# sh.net
KiCad netlist of a schematic drawn in EAGLE
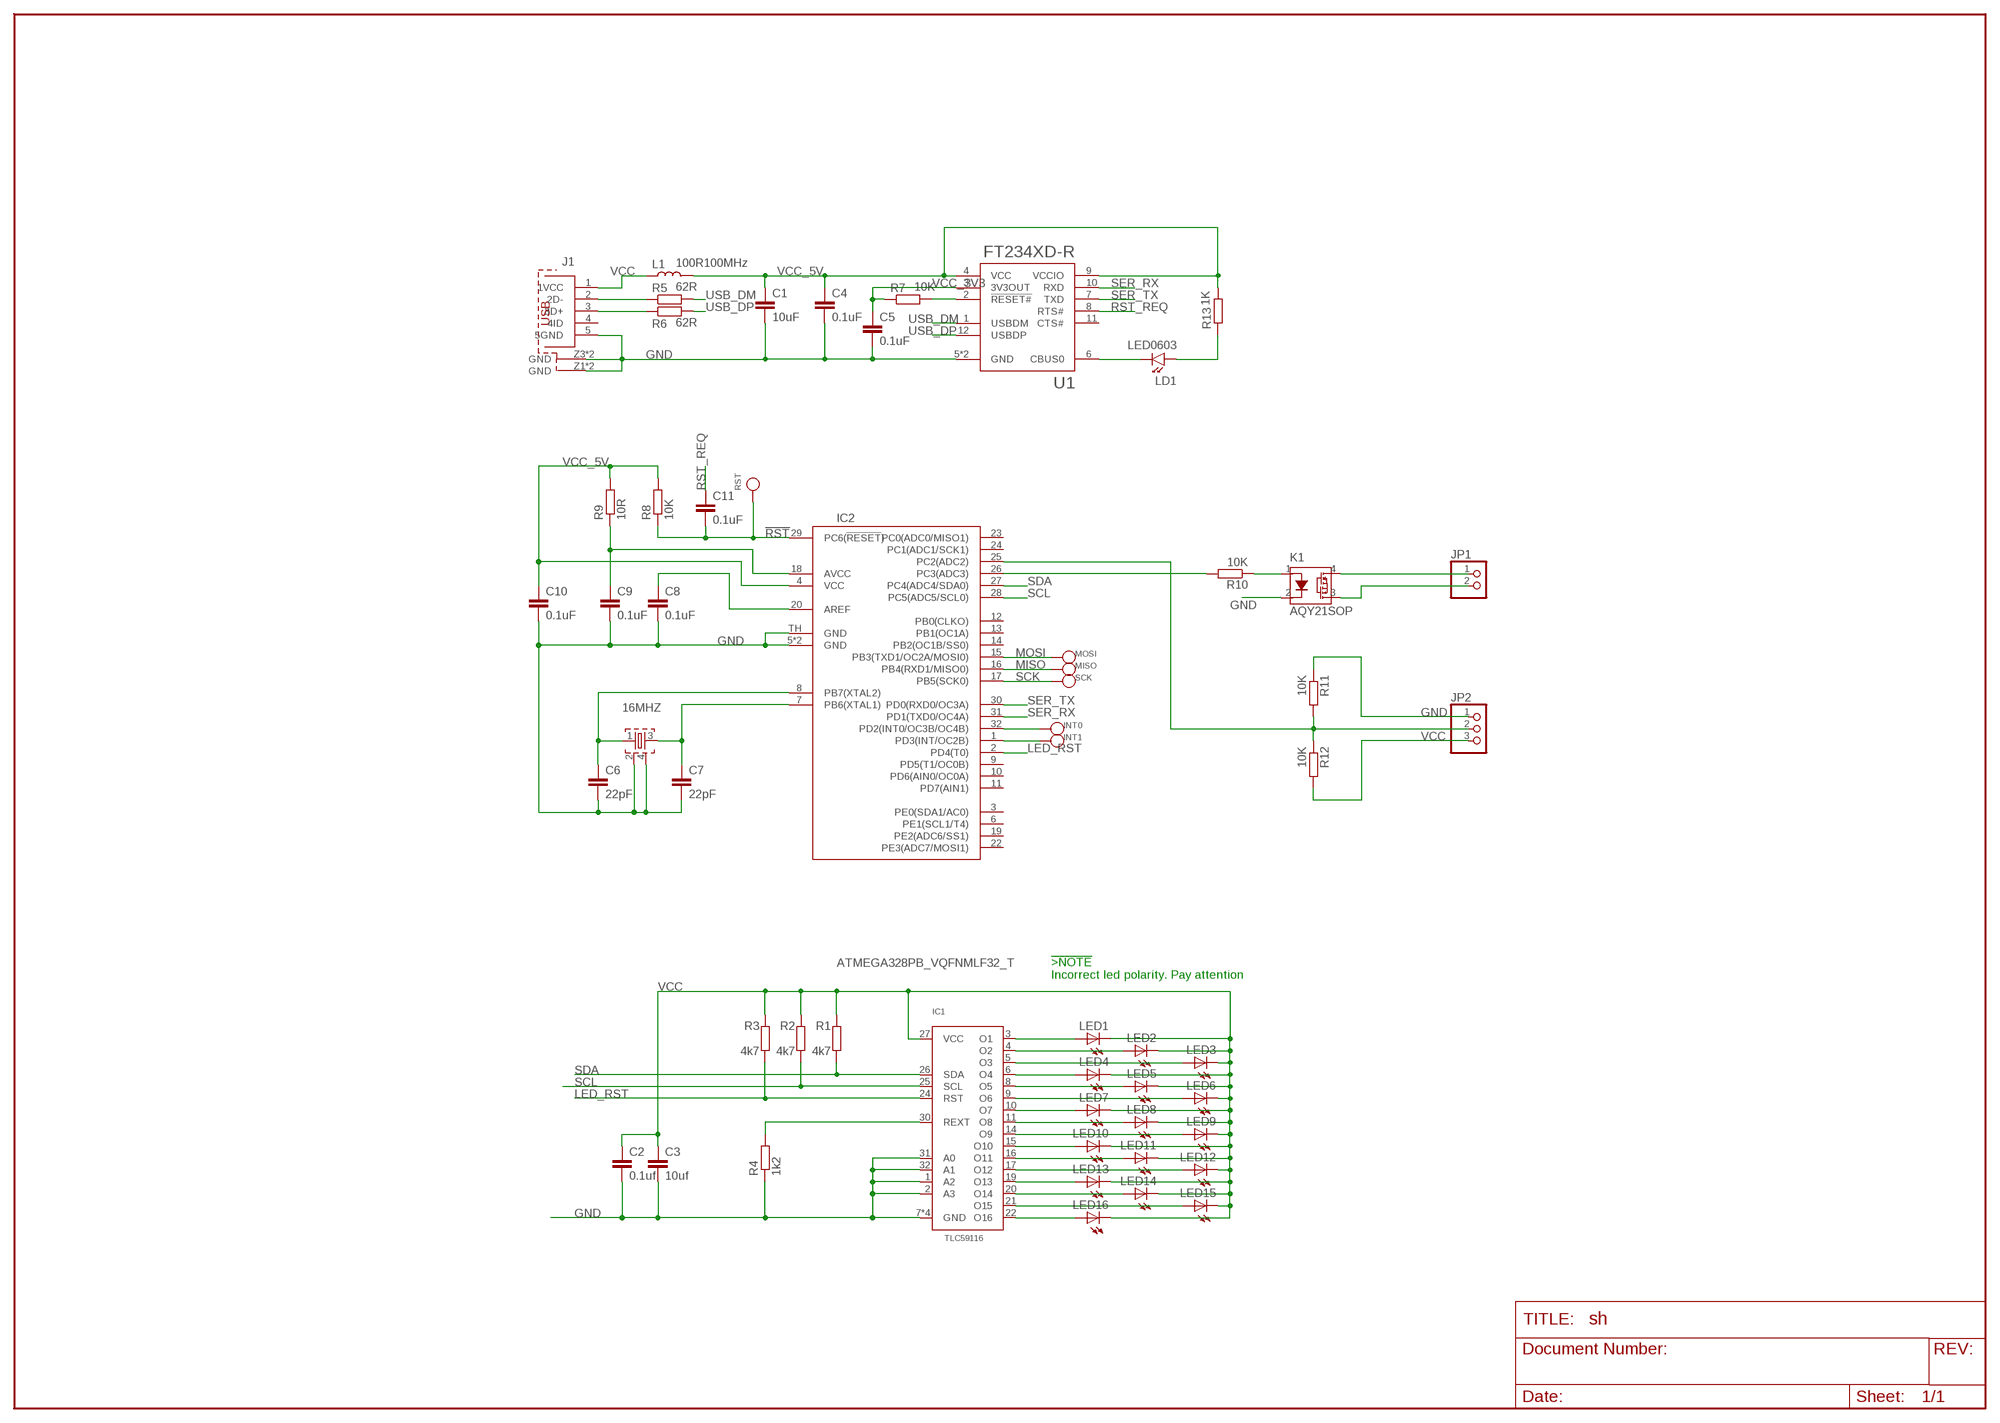
[diagram p0: schematic, sheet 1]

(export (version "E")
  (design (tool "Eeschema 10.0.6"))
  (components
    (comp (ref "16MHZ")
      (value "QUARTZ_ZQ")
      (footprint "eagle-import:QUARTZ_3X3MM")
      (libsource (lib "eagle-import") (part "QUARTZ_ZQ"))
    )
    (comp (ref "C1")
      (value "10uF")
      (footprint "eagle-import:1206")
      (libsource (lib "eagle-import") (part "SMD_C1206"))
    )
    (comp (ref "C2")
      (value "0.1uf")
      (footprint "eagle-import:0603")
      (libsource (lib "eagle-import") (part "SMD_C0603"))
    )
    (comp (ref "C3")
      (value "10uf")
      (footprint "eagle-import:1206")
      (libsource (lib "eagle-import") (part "SMD_C1206"))
    )
    (comp (ref "C4")
      (value "0.1uF")
      (footprint "eagle-import:0603")
      (libsource (lib "eagle-import") (part "SMD_C0603"))
    )
    (comp (ref "C5")
      (value "0.1uF")
      (footprint "eagle-import:0603")
      (libsource (lib "eagle-import") (part "SMD_C0603"))
    )
    (comp (ref "C6")
      (value "22pF")
      (footprint "eagle-import:0603")
      (libsource (lib "eagle-import") (part "SMD_C0603"))
    )
    (comp (ref "C7")
      (value "22pF")
      (footprint "eagle-import:0603")
      (libsource (lib "eagle-import") (part "SMD_C0603"))
    )
    (comp (ref "C8")
      (value "0.1uF")
      (footprint "eagle-import:0603")
      (libsource (lib "eagle-import") (part "SMD_C0603"))
    )
    (comp (ref "C9")
      (value "0.1uF")
      (footprint "eagle-import:0603")
      (libsource (lib "eagle-import") (part "SMD_C0603"))
    )
    (comp (ref "C10")
      (value "0.1uF")
      (footprint "eagle-import:0603")
      (libsource (lib "eagle-import") (part "SMD_C0603"))
    )
    (comp (ref "C11")
      (value "0.1uF")
      (footprint "eagle-import:0603")
      (libsource (lib "eagle-import") (part "SMD_C0603"))
    )
    (comp (ref "IC1")
      (value "TLC59116")
      (footprint "eagle-import:MLF32-TH")
      (libsource (lib "eagle-import") (part "TLC59116"))
    )
    (comp (ref "IC2")
      (value "ATMEGA328PB_VQFNMLF32_T")
      (footprint "eagle-import:MLF32-TH")
      (libsource (lib "eagle-import") (part "ATMEGA328PB_VQFNMLF32_T"))
    )
    (comp (ref "INT0")
      (value "TEST_POINT_D2MM")
      (footprint "eagle-import:TP")
      (libsource (lib "eagle-import") (part "TEST_POINT_D2MM"))
    )
    (comp (ref "INT1")
      (value "TEST_POINT_D2MM")
      (footprint "eagle-import:TP")
      (libsource (lib "eagle-import") (part "TEST_POINT_D2MM"))
    )
    (comp (ref "J1")
      (value "MINI_USB_TYP_B_@")
      (footprint "eagle-import:65100516121")
      (libsource (lib "eagle-import") (part "MINI_USB_TYP_B_@"))
    )
    (comp (ref "JP1")
      (value "PINHD-1X2LIGHT")
      (footprint "eagle-import:2X01")
      (libsource (lib "eagle-import") (part "PINHD-1X2LIGHT"))
    )
    (comp (ref "JP2")
      (value "PINHD-1X3_LIGHT")
      (footprint "eagle-import:3X01")
      (libsource (lib "eagle-import") (part "PINHD-1X3_LIGHT"))
    )
    (comp (ref "K1")
      (value "AQY21SOP")
      (footprint "eagle-import:SOP04")
      (libsource (lib "eagle-import") (part "AQYSOP21"))
    )
    (comp (ref "L1")
      (value "100R100MHz")
      (footprint "eagle-import:0805")
      (libsource (lib "eagle-import") (part "SMD_L"))
    )
    (comp (ref "LD1")
      (value "LED0603")
      (footprint "eagle-import:0603_P")
      (libsource (lib "eagle-import") (part "LED0603"))
    )
    (comp (ref "LED1")
      (value "LED2KA-3528ASYC")
      (footprint "eagle-import:KA-3528ASYC")
      (libsource (lib "eagle-import") (part "LED2KA-3528ASYC"))
    )
    (comp (ref "LED2")
      (value "LED2KA-3528ASYC")
      (footprint "eagle-import:KA-3528ASYC")
      (libsource (lib "eagle-import") (part "LED2KA-3528ASYC"))
    )
    (comp (ref "LED3")
      (value "LED2KA-3528ASYC")
      (footprint "eagle-import:KA-3528ASYC")
      (libsource (lib "eagle-import") (part "LED2KA-3528ASYC"))
    )
    (comp (ref "LED4")
      (value "LED2KA-3528ASYC")
      (footprint "eagle-import:KA-3528ASYC")
      (libsource (lib "eagle-import") (part "LED2KA-3528ASYC"))
    )
    (comp (ref "LED5")
      (value "LED2KA-3528ASYC")
      (footprint "eagle-import:KA-3528ASYC")
      (libsource (lib "eagle-import") (part "LED2KA-3528ASYC"))
    )
    (comp (ref "LED6")
      (value "LED2KA-3528ASYC")
      (footprint "eagle-import:KA-3528ASYC")
      (libsource (lib "eagle-import") (part "LED2KA-3528ASYC"))
    )
    (comp (ref "LED7")
      (value "LED2KA-3528ASYC")
      (footprint "eagle-import:KA-3528ASYC")
      (libsource (lib "eagle-import") (part "LED2KA-3528ASYC"))
    )
    (comp (ref "LED8")
      (value "LED2KA-3528ASYC")
      (footprint "eagle-import:KA-3528ASYC")
      (libsource (lib "eagle-import") (part "LED2KA-3528ASYC"))
    )
    (comp (ref "LED9")
      (value "LED2KA-3528ASYC")
      (footprint "eagle-import:KA-3528ASYC")
      (libsource (lib "eagle-import") (part "LED2KA-3528ASYC"))
    )
    (comp (ref "LED10")
      (value "LED2KA-3528ASYC")
      (footprint "eagle-import:KA-3528ASYC")
      (libsource (lib "eagle-import") (part "LED2KA-3528ASYC"))
    )
    (comp (ref "LED11")
      (value "LED2KA-3528ASYC")
      (footprint "eagle-import:KA-3528ASYC")
      (libsource (lib "eagle-import") (part "LED2KA-3528ASYC"))
    )
    (comp (ref "LED12")
      (value "LED2KA-3528ASYC")
      (footprint "eagle-import:KA-3528ASYC")
      (libsource (lib "eagle-import") (part "LED2KA-3528ASYC"))
    )
    (comp (ref "LED13")
      (value "LED2KA-3528ASYC")
      (footprint "eagle-import:KA-3528ASYC")
      (libsource (lib "eagle-import") (part "LED2KA-3528ASYC"))
    )
    (comp (ref "LED14")
      (value "LED2KA-3528ASYC")
      (footprint "eagle-import:KA-3528ASYC")
      (libsource (lib "eagle-import") (part "LED2KA-3528ASYC"))
    )
    (comp (ref "LED15")
      (value "LED2KA-3528ASYC")
      (footprint "eagle-import:KA-3528ASYC")
      (libsource (lib "eagle-import") (part "LED2KA-3528ASYC"))
    )
    (comp (ref "LED16")
      (value "LED2KA-3528ASYC")
      (footprint "eagle-import:KA-3528ASYC")
      (libsource (lib "eagle-import") (part "LED2KA-3528ASYC"))
    )
    (comp (ref "MISO")
      (value "TEST_POINT_D2MM")
      (footprint "eagle-import:TP")
      (libsource (lib "eagle-import") (part "TEST_POINT_D2MM"))
    )
    (comp (ref "MOSI")
      (value "TEST_POINT_D2MM")
      (footprint "eagle-import:TP")
      (libsource (lib "eagle-import") (part "TEST_POINT_D2MM"))
    )
    (comp (ref "R1")
      (value "4k7")
      (footprint "eagle-import:0603")
      (libsource (lib "eagle-import") (part "SMD_R0603"))
    )
    (comp (ref "R2")
      (value "4k7")
      (footprint "eagle-import:0603")
      (libsource (lib "eagle-import") (part "SMD_R0603"))
    )
    (comp (ref "R3")
      (value "4k7")
      (footprint "eagle-import:0603")
      (libsource (lib "eagle-import") (part "SMD_R0603"))
    )
    (comp (ref "R4")
      (value "1k2")
      (footprint "eagle-import:0603")
      (libsource (lib "eagle-import") (part "SMD_R0603"))
    )
    (comp (ref "R5")
      (value "62R")
      (footprint "eagle-import:0603")
      (libsource (lib "eagle-import") (part "SMD_R0603"))
    )
    (comp (ref "R6")
      (value "62R")
      (footprint "eagle-import:0603")
      (libsource (lib "eagle-import") (part "SMD_R0603"))
    )
    (comp (ref "R7")
      (value "10K")
      (footprint "eagle-import:0603")
      (libsource (lib "eagle-import") (part "SMD_R0603"))
    )
    (comp (ref "R8")
      (value "10K")
      (footprint "eagle-import:0603")
      (libsource (lib "eagle-import") (part "SMD_R0603"))
    )
    (comp (ref "R9")
      (value "10R")
      (footprint "eagle-import:0603")
      (libsource (lib "eagle-import") (part "SMD_R0603"))
    )
    (comp (ref "R10")
      (value "10K")
      (footprint "eagle-import:0603")
      (libsource (lib "eagle-import") (part "SMD_R0603"))
    )
    (comp (ref "R11")
      (value "10K")
      (footprint "eagle-import:0603")
      (libsource (lib "eagle-import") (part "SMD_R0603"))
    )
    (comp (ref "R12")
      (value "10K")
      (footprint "eagle-import:0603")
      (libsource (lib "eagle-import") (part "SMD_R0603"))
    )
    (comp (ref "R13")
      (value "1K")
      (footprint "eagle-import:0603")
      (libsource (lib "eagle-import") (part "SMD_R0603"))
    )
    (comp (ref "RST")
      (value "TEST_POINT_D2MM")
      (footprint "eagle-import:TP")
      (libsource (lib "eagle-import") (part "TEST_POINT_D2MM"))
    )
    (comp (ref "SCK")
      (value "TEST_POINT_D2MM")
      (footprint "eagle-import:TP")
      (libsource (lib "eagle-import") (part "TEST_POINT_D2MM"))
    )
    (comp (ref "U1")
      (value "FT234XD-R")
      (footprint "eagle-import:IC_FT234XD-R")
      (fields (field (name "MF") "FTDI,"))
      (libsource (lib "eagle-import") (part "FT234XD-R"))
    )
  )
  (nets
    (net (code "1") (name "/GND") (class "Default")
      (node (ref "16MHZ") (pin "2") (pinfunction "2_2") (pintype "passive"))
      (node (ref "16MHZ") (pin "4") (pinfunction "4_4") (pintype "passive"))
      (node (ref "C1") (pin "2") (pinfunction "2_2") (pintype "passive"))
      (node (ref "C10") (pin "2") (pinfunction "2_2") (pintype "passive"))
      (node (ref "C2") (pin "2") (pinfunction "2_2") (pintype "passive"))
      (node (ref "C3") (pin "2") (pinfunction "2_2") (pintype "passive"))
      (node (ref "C4") (pin "2") (pinfunction "2_2") (pintype "passive"))
      (node (ref "C5") (pin "2") (pinfunction "2_2") (pintype "passive"))
      (node (ref "C6") (pin "2") (pinfunction "2_2") (pintype "passive"))
      (node (ref "C7") (pin "2") (pinfunction "2_2") (pintype "passive"))
      (node (ref "C8") (pin "2") (pinfunction "2_2") (pintype "passive"))
      (node (ref "C9") (pin "2") (pinfunction "2_2") (pintype "passive"))
      (node (ref "IC1") (pin "1") (pinfunction "A2_1") (pintype "bidirectional"))
      (node (ref "IC1") (pin "18") (pinfunction "GND_18") (pintype "bidirectional"))
      (node (ref "IC1") (pin "2") (pinfunction "A3_2") (pintype "bidirectional"))
      (node (ref "IC1") (pin "23") (pinfunction "GND_23") (pintype "bidirectional"))
      (node (ref "IC1") (pin "31") (pinfunction "A0_31") (pintype "bidirectional"))
      (node (ref "IC1") (pin "32") (pinfunction "A1_32") (pintype "bidirectional"))
      (node (ref "IC1") (pin "7") (pinfunction "GND_7") (pintype "bidirectional"))
      (node (ref "IC1") (pin "TH") (pinfunction "GND_TH") (pintype "bidirectional"))
      (node (ref "IC2") (pin "21") (pinfunction "GND_21") (pintype "power_in"))
      (node (ref "IC2") (pin "5") (pinfunction "GND_5") (pintype "power_in"))
      (node (ref "IC2") (pin "TH") (pinfunction "GND_TH") (pintype "power_in"))
      (node (ref "J1") (pin "5") (pinfunction "5GND_5") (pintype "passive"))
      (node (ref "J1") (pin "Z1") (pinfunction "GND_Z1") (pintype "bidirectional"))
      (node (ref "J1") (pin "Z2") (pinfunction "GND_Z2") (pintype "bidirectional"))
      (node (ref "J1") (pin "Z3") (pinfunction "GND_Z3") (pintype "bidirectional"))
      (node (ref "J1") (pin "Z4") (pinfunction "GND_Z4") (pintype "bidirectional"))
      (node (ref "JP2") (pin "1") (pinfunction "1_1") (pintype "passive"))
      (node (ref "K1") (pin "2") (pinfunction "K_2") (pintype "passive"))
      (node (ref "R11") (pin "1") (pinfunction "1_1") (pintype "passive"))
      (node (ref "R4") (pin "1") (pinfunction "1_1") (pintype "passive"))
      (node (ref "U1") (pin "13") (pinfunction "GND_13") (pintype "power_in"))
      (node (ref "U1") (pin "5") (pinfunction "GND_5") (pintype "power_in"))
    )
    (net (code "2") (name "/LED_RST") (class "Default")
      (node (ref "IC1") (pin "24") (pinfunction "RST_24") (pintype "bidirectional"))
      (node (ref "IC2") (pin "2") (pinfunction "PD4(T0)_2") (pintype "bidirectional"))
      (node (ref "R3") (pin "1") (pinfunction "1_1") (pintype "passive"))
    )
    (net (code "3") (name "/MISO") (class "Default")
      (node (ref "IC2") (pin "16") (pinfunction "PB4(RXD1/MISO0)_16") (pintype "bidirectional"))
      (node (ref "MISO") (pin "P$1") (pinfunction "1_P$1") (pintype "bidirectional"))
    )
    (net (code "4") (name "/MOSI") (class "Default")
      (node (ref "IC2") (pin "15") (pinfunction "PB3(TXD1/OC2A/MOSI0)_15") (pintype "bidirectional"))
      (node (ref "MOSI") (pin "P$1") (pinfunction "1_P$1") (pintype "bidirectional"))
    )
    (net (code "5") (name "/RST_REQ") (class "Default")
      (node (ref "C11") (pin "1") (pinfunction "1_1") (pintype "passive"))
      (node (ref "U1") (pin "8") (pinfunction "RTS#_8") (pintype "output"))
    )
    (net (code "6") (name "/SCK") (class "Default")
      (node (ref "IC2") (pin "17") (pinfunction "PB5(SCK0)_17") (pintype "bidirectional"))
      (node (ref "SCK") (pin "P$1") (pinfunction "1_P$1") (pintype "bidirectional"))
    )
    (net (code "7") (name "/SCL") (class "Default")
      (node (ref "IC1") (pin "25") (pinfunction "SCL_25") (pintype "bidirectional"))
      (node (ref "IC2") (pin "28") (pinfunction "PC5(ADC5/SCL0)_28") (pintype "bidirectional"))
      (node (ref "R2") (pin "1") (pinfunction "1_1") (pintype "passive"))
    )
    (net (code "8") (name "/SDA") (class "Default")
      (node (ref "IC1") (pin "26") (pinfunction "SDA_26") (pintype "bidirectional"))
      (node (ref "IC2") (pin "27") (pinfunction "PC4(ADC4/SDA0)_27") (pintype "bidirectional"))
      (node (ref "R1") (pin "1") (pinfunction "1_1") (pintype "passive"))
    )
    (net (code "9") (name "/SER_RX") (class "Default")
      (node (ref "IC2") (pin "31") (pinfunction "PD1(TXD0/OC4A)_31") (pintype "bidirectional"))
      (node (ref "U1") (pin "10") (pinfunction "RXD_10") (pintype "input"))
    )
    (net (code "10") (name "/SER_TX") (class "Default")
      (node (ref "IC2") (pin "30") (pinfunction "PD0(RXD0/OC3A)_30") (pintype "bidirectional"))
      (node (ref "U1") (pin "7") (pinfunction "TXD_7") (pintype "output"))
    )
    (net (code "11") (name "/USB_DM") (class "Default")
      (node (ref "R5") (pin "2") (pinfunction "2_2") (pintype "passive"))
      (node (ref "U1") (pin "1") (pinfunction "USBDM_1") (pintype "bidirectional"))
    )
    (net (code "12") (name "/USB_DP") (class "Default")
      (node (ref "R6") (pin "2") (pinfunction "2_2") (pintype "passive"))
      (node (ref "U1") (pin "12") (pinfunction "USBDP_12") (pintype "bidirectional"))
    )
    (net (code "13") (name "/VCC") (class "Default")
      (node (ref "C2") (pin "1") (pinfunction "1_1") (pintype "passive"))
      (node (ref "C3") (pin "1") (pinfunction "1_1") (pintype "passive"))
      (node (ref "IC1") (pin "27") (pinfunction "VCC_27") (pintype "bidirectional"))
      (node (ref "J1") (pin "1") (pinfunction "1VCC_1") (pintype "passive"))
      (node (ref "JP2") (pin "3") (pinfunction "3_3") (pintype "passive"))
      (node (ref "L1") (pin "1") (pinfunction "1_1") (pintype "passive"))
      (node (ref "LED1") (pin "C") (pinfunction "C_C") (pintype "passive"))
      (node (ref "LED10") (pin "C") (pinfunction "C_C") (pintype "passive"))
      (node (ref "LED11") (pin "C") (pinfunction "C_C") (pintype "passive"))
      (node (ref "LED12") (pin "C") (pinfunction "C_C") (pintype "passive"))
      (node (ref "LED13") (pin "C") (pinfunction "C_C") (pintype "passive"))
      (node (ref "LED14") (pin "C") (pinfunction "C_C") (pintype "passive"))
      (node (ref "LED15") (pin "C") (pinfunction "C_C") (pintype "passive"))
      (node (ref "LED16") (pin "C") (pinfunction "C_C") (pintype "passive"))
      (node (ref "LED2") (pin "C") (pinfunction "C_C") (pintype "passive"))
      (node (ref "LED3") (pin "C") (pinfunction "C_C") (pintype "passive"))
      (node (ref "LED4") (pin "C") (pinfunction "C_C") (pintype "passive"))
      (node (ref "LED5") (pin "C") (pinfunction "C_C") (pintype "passive"))
      (node (ref "LED6") (pin "C") (pinfunction "C_C") (pintype "passive"))
      (node (ref "LED7") (pin "C") (pinfunction "C_C") (pintype "passive"))
      (node (ref "LED8") (pin "C") (pinfunction "C_C") (pintype "passive"))
      (node (ref "LED9") (pin "C") (pinfunction "C_C") (pintype "passive"))
      (node (ref "R1") (pin "2") (pinfunction "2_2") (pintype "passive"))
      (node (ref "R12") (pin "2") (pinfunction "2_2") (pintype "passive"))
      (node (ref "R2") (pin "2") (pinfunction "2_2") (pintype "passive"))
      (node (ref "R3") (pin "2") (pinfunction "2_2") (pintype "passive"))
    )
    (net (code "14") (name "/VCC_3V3") (class "Default")
      (node (ref "C5") (pin "1") (pinfunction "1_1") (pintype "passive"))
      (node (ref "R7") (pin "1") (pinfunction "1_1") (pintype "passive"))
      (node (ref "U1") (pin "3") (pinfunction "3V3OUT_3") (pintype "output"))
    )
    (net (code "15") (name "/VCC_5V") (class "Default")
      (node (ref "C1") (pin "1") (pinfunction "1_1") (pintype "passive"))
      (node (ref "C10") (pin "1") (pinfunction "1_1") (pintype "passive"))
      (node (ref "C4") (pin "1") (pinfunction "1_1") (pintype "passive"))
      (node (ref "IC2") (pin "4") (pinfunction "VCC_4") (pintype "power_in"))
      (node (ref "L1") (pin "2") (pinfunction "2_2") (pintype "passive"))
      (node (ref "R13") (pin "2") (pinfunction "2_2") (pintype "passive"))
      (node (ref "R8") (pin "2") (pinfunction "2_2") (pintype "passive"))
      (node (ref "R9") (pin "2") (pinfunction "2_2") (pintype "passive"))
      (node (ref "U1") (pin "4") (pinfunction "VCC_4") (pintype "power_in"))
      (node (ref "U1") (pin "9") (pinfunction "VCCIO_9") (pintype "power_in"))
    )
    (net (code "16") (name "/~{RST}") (class "Default")
      (node (ref "C11") (pin "2") (pinfunction "2_2") (pintype "passive"))
      (node (ref "IC2") (pin "29") (pinfunction "PC6(~{RESET})_29") (pintype "bidirectional"))
      (node (ref "R8") (pin "1") (pinfunction "1_1") (pintype "passive"))
      (node (ref "RST") (pin "P$1") (pinfunction "1_P$1") (pintype "bidirectional"))
    )
    (net (code "17") (name "Net-(IC1-O1)") (class "Default")
      (node (ref "IC1") (pin "3") (pinfunction "O1_3") (pintype "bidirectional"))
      (node (ref "LED1") (pin "A") (pinfunction "A_A") (pintype "passive"))
    )
    (net (code "18") (name "Net-(IC1-O2)") (class "Default")
      (node (ref "IC1") (pin "4") (pinfunction "O2_4") (pintype "bidirectional"))
      (node (ref "LED2") (pin "A") (pinfunction "A_A") (pintype "passive"))
    )
    (net (code "19") (name "Net-(IC1-O3)") (class "Default")
      (node (ref "IC1") (pin "5") (pinfunction "O3_5") (pintype "bidirectional"))
      (node (ref "LED3") (pin "A") (pinfunction "A_A") (pintype "passive"))
    )
    (net (code "20") (name "Net-(IC1-O4)") (class "Default")
      (node (ref "IC1") (pin "6") (pinfunction "O4_6") (pintype "bidirectional"))
      (node (ref "LED4") (pin "A") (pinfunction "A_A") (pintype "passive"))
    )
    (net (code "21") (name "Net-(IC1-O5)") (class "Default")
      (node (ref "IC1") (pin "8") (pinfunction "O5_8") (pintype "bidirectional"))
      (node (ref "LED5") (pin "A") (pinfunction "A_A") (pintype "passive"))
    )
    (net (code "22") (name "Net-(IC1-O6)") (class "Default")
      (node (ref "IC1") (pin "9") (pinfunction "O6_9") (pintype "bidirectional"))
      (node (ref "LED6") (pin "A") (pinfunction "A_A") (pintype "passive"))
    )
    (net (code "23") (name "Net-(IC1-O7)") (class "Default")
      (node (ref "IC1") (pin "10") (pinfunction "O7_10") (pintype "bidirectional"))
      (node (ref "LED7") (pin "A") (pinfunction "A_A") (pintype "passive"))
    )
    (net (code "24") (name "Net-(IC1-O8)") (class "Default")
      (node (ref "IC1") (pin "11") (pinfunction "O8_11") (pintype "bidirectional"))
      (node (ref "LED8") (pin "A") (pinfunction "A_A") (pintype "passive"))
    )
    (net (code "25") (name "Net-(IC1-O9)") (class "Default")
      (node (ref "IC1") (pin "14") (pinfunction "O9_14") (pintype "bidirectional"))
      (node (ref "LED9") (pin "A") (pinfunction "A_A") (pintype "passive"))
    )
    (net (code "26") (name "Net-(IC1-O10)") (class "Default")
      (node (ref "IC1") (pin "15") (pinfunction "O10_15") (pintype "bidirectional"))
      (node (ref "LED10") (pin "A") (pinfunction "A_A") (pintype "passive"))
    )
    (net (code "27") (name "Net-(IC1-O11)") (class "Default")
      (node (ref "IC1") (pin "16") (pinfunction "O11_16") (pintype "bidirectional"))
      (node (ref "LED11") (pin "A") (pinfunction "A_A") (pintype "passive"))
    )
    (net (code "28") (name "Net-(IC1-O12)") (class "Default")
      (node (ref "IC1") (pin "17") (pinfunction "O12_17") (pintype "bidirectional"))
      (node (ref "LED12") (pin "A") (pinfunction "A_A") (pintype "passive"))
    )
    (net (code "29") (name "Net-(IC1-O13)") (class "Default")
      (node (ref "IC1") (pin "19") (pinfunction "O13_19") (pintype "bidirectional"))
      (node (ref "LED13") (pin "A") (pinfunction "A_A") (pintype "passive"))
    )
    (net (code "30") (name "Net-(IC1-O14)") (class "Default")
      (node (ref "IC1") (pin "20") (pinfunction "O14_20") (pintype "bidirectional"))
      (node (ref "LED14") (pin "A") (pinfunction "A_A") (pintype "passive"))
    )
    (net (code "31") (name "Net-(IC1-O15)") (class "Default")
      (node (ref "IC1") (pin "21") (pinfunction "O15_21") (pintype "bidirectional"))
      (node (ref "LED15") (pin "A") (pinfunction "A_A") (pintype "passive"))
    )
    (net (code "32") (name "Net-(IC1-O16)") (class "Default")
      (node (ref "IC1") (pin "22") (pinfunction "O16_22") (pintype "bidirectional"))
      (node (ref "LED16") (pin "A") (pinfunction "A_A") (pintype "passive"))
    )
    (net (code "33") (name "Net-(IC1-REXT)") (class "Default")
      (node (ref "IC1") (pin "30") (pinfunction "REXT_30") (pintype "bidirectional"))
      (node (ref "R4") (pin "2") (pinfunction "2_2") (pintype "passive"))
    )
    (net (code "34") (name "Net-(IC2-AREF)") (class "Default")
      (node (ref "C8") (pin "1") (pinfunction "1_1") (pintype "passive"))
      (node (ref "IC2") (pin "20") (pinfunction "AREF_20") (pintype "passive"))
    )
    (net (code "35") (name "Net-(IC2-AVCC)") (class "Default")
      (node (ref "C9") (pin "1") (pinfunction "1_1") (pintype "passive"))
      (node (ref "IC2") (pin "18") (pinfunction "AVCC_18") (pintype "power_in"))
      (node (ref "R9") (pin "1") (pinfunction "1_1") (pintype "passive"))
    )
    (net (code "36") (name "Net-(IC2-PB6(XTAL1))") (class "Default")
      (node (ref "16MHZ") (pin "3") (pinfunction "3_3") (pintype "passive"))
      (node (ref "C7") (pin "1") (pinfunction "1_1") (pintype "passive"))
      (node (ref "IC2") (pin "7") (pinfunction "PB6(XTAL1)_7") (pintype "bidirectional"))
    )
    (net (code "37") (name "Net-(IC2-PB7(XTAL2))") (class "Default")
      (node (ref "16MHZ") (pin "1") (pinfunction "1_1") (pintype "passive"))
      (node (ref "C6") (pin "1") (pinfunction "1_1") (pintype "passive"))
      (node (ref "IC2") (pin "8") (pinfunction "PB7(XTAL2)_8") (pintype "bidirectional"))
    )
    (net (code "38") (name "Net-(IC2-PC2(ADC2))") (class "Default")
      (node (ref "IC2") (pin "25") (pinfunction "PC2(ADC2)_25") (pintype "bidirectional"))
      (node (ref "JP2") (pin "2") (pinfunction "2_2") (pintype "passive"))
      (node (ref "R11") (pin "2") (pinfunction "2_2") (pintype "passive"))
      (node (ref "R12") (pin "1") (pinfunction "1_1") (pintype "passive"))
    )
    (net (code "39") (name "Net-(IC2-PC3(ADC3))") (class "Default")
      (node (ref "IC2") (pin "26") (pinfunction "PC3(ADC3)_26") (pintype "bidirectional"))
      (node (ref "R10") (pin "2") (pinfunction "2_2") (pintype "passive"))
    )
    (net (code "40") (name "Net-(IC2-PD2(INT0{slash}OC3B{slash}OC4B))") (class "Default")
      (node (ref "IC2") (pin "32") (pinfunction "PD2(INT0/OC3B/OC4B)_32") (pintype "bidirectional"))
      (node (ref "INT0") (pin "P$1") (pinfunction "1_P$1") (pintype "bidirectional"))
    )
    (net (code "41") (name "Net-(IC2-PD3(INT{slash}OC2B))") (class "Default")
      (node (ref "IC2") (pin "1") (pinfunction "PD3(INT/OC2B)_1") (pintype "bidirectional"))
      (node (ref "INT1") (pin "P$1") (pinfunction "1_P$1") (pintype "bidirectional"))
    )
    (net (code "42") (name "Net-(J1-2D-)") (class "Default")
      (node (ref "J1") (pin "2") (pinfunction "2D-_2") (pintype "passive"))
      (node (ref "R5") (pin "1") (pinfunction "1_1") (pintype "passive"))
    )
    (net (code "43") (name "Net-(J1-3D+)") (class "Default")
      (node (ref "J1") (pin "3") (pinfunction "3D+_3") (pintype "passive"))
      (node (ref "R6") (pin "1") (pinfunction "1_1") (pintype "passive"))
    )
    (net (code "44") (name "Net-(K1-A)") (class "Default")
      (node (ref "K1") (pin "1") (pinfunction "A_1") (pintype "passive"))
      (node (ref "R10") (pin "1") (pinfunction "1_1") (pintype "passive"))
    )
    (net (code "45") (name "Net-(K1-DS1)") (class "Default")
      (node (ref "JP1") (pin "1") (pinfunction "1_1") (pintype "passive"))
      (node (ref "K1") (pin "4") (pinfunction "DS1_4") (pintype "passive"))
    )
    (net (code "46") (name "Net-(K1-DS2)") (class "Default")
      (node (ref "JP1") (pin "2") (pinfunction "2_2") (pintype "passive"))
      (node (ref "K1") (pin "3") (pinfunction "DS2_3") (pintype "passive"))
    )
    (net (code "47") (name "Net-(LD1-A)") (class "Default")
      (node (ref "LD1") (pin "2") (pinfunction "A_2") (pintype "bidirectional"))
      (node (ref "R13") (pin "1") (pinfunction "1_1") (pintype "passive"))
    )
    (net (code "48") (name "Net-(LD1-K)") (class "Default")
      (node (ref "LD1") (pin "1") (pinfunction "K_1") (pintype "bidirectional"))
      (node (ref "U1") (pin "6") (pinfunction "CBUS0_6") (pintype "bidirectional"))
    )
    (net (code "49") (name "Net-(U1-~{RESET#})") (class "Default")
      (node (ref "R7") (pin "2") (pinfunction "2_2") (pintype "passive"))
      (node (ref "U1") (pin "2") (pinfunction "~{RESET#}_2") (pintype "input"))
    )
    (net (code "50") (name "unconnected-(IC2-PB0(CLKO)-Pad12)") (class "Default")
      (node (ref "IC2") (pin "12") (pinfunction "PB0(CLKO)_12") (pintype "bidirectional"))
    )
    (net (code "51") (name "unconnected-(IC2-PB1(OC1A)-Pad13)") (class "Default")
      (node (ref "IC2") (pin "13") (pinfunction "PB1(OC1A)_13") (pintype "bidirectional"))
    )
    (net (code "52") (name "unconnected-(IC2-PB2(OC1B{slash}SS0)-Pad14)") (class "Default")
      (node (ref "IC2") (pin "14") (pinfunction "PB2(OC1B/SS0)_14") (pintype "bidirectional"))
    )
    (net (code "53") (name "unconnected-(IC2-PC0(ADC0{slash}MISO1)-Pad23)") (class "Default")
      (node (ref "IC2") (pin "23") (pinfunction "PC0(ADC0/MISO1)_23") (pintype "bidirectional"))
    )
    (net (code "54") (name "unconnected-(IC2-PC1(ADC1{slash}SCK1)-Pad24)") (class "Default")
      (node (ref "IC2") (pin "24") (pinfunction "PC1(ADC1/SCK1)_24") (pintype "bidirectional"))
    )
    (net (code "55") (name "unconnected-(IC2-PD5(T1{slash}OC0B)-Pad9)") (class "Default")
      (node (ref "IC2") (pin "9") (pinfunction "PD5(T1/OC0B)_9") (pintype "bidirectional"))
    )
    (net (code "56") (name "unconnected-(IC2-PD6(AIN0{slash}OC0A)-Pad10)") (class "Default")
      (node (ref "IC2") (pin "10") (pinfunction "PD6(AIN0/OC0A)_10") (pintype "bidirectional"))
    )
    (net (code "57") (name "unconnected-(IC2-PD7(AIN1)-Pad11)") (class "Default")
      (node (ref "IC2") (pin "11") (pinfunction "PD7(AIN1)_11") (pintype "bidirectional"))
    )
    (net (code "58") (name "unconnected-(IC2-PE0(SDA1{slash}AC0)-Pad3)") (class "Default")
      (node (ref "IC2") (pin "3") (pinfunction "PE0(SDA1/AC0)_3") (pintype "bidirectional"))
    )
    (net (code "59") (name "unconnected-(IC2-PE1(SCL1{slash}T4)-Pad6)") (class "Default")
      (node (ref "IC2") (pin "6") (pinfunction "PE1(SCL1/T4)_6") (pintype "bidirectional"))
    )
    (net (code "60") (name "unconnected-(IC2-PE2(ADC6{slash}SS1)-Pad19)") (class "Default")
      (node (ref "IC2") (pin "19") (pinfunction "PE2(ADC6/SS1)_19") (pintype "bidirectional"))
    )
    (net (code "61") (name "unconnected-(IC2-PE3(ADC7{slash}MOSI1)-Pad22)") (class "Default")
      (node (ref "IC2") (pin "22") (pinfunction "PE3(ADC7/MOSI1)_22") (pintype "bidirectional"))
    )
    (net (code "62") (name "unconnected-(J1-4ID-Pad4)") (class "Default")
      (node (ref "J1") (pin "4") (pinfunction "4ID_4") (pintype "passive"))
    )
    (net (code "63") (name "unconnected-(U1-CTS#-Pad11)") (class "Default")
      (node (ref "U1") (pin "11") (pinfunction "CTS#_11") (pintype "input"))
    )
  )
)
